# esp-tom.net
KiCad netlist of a schematic drawn in EAGLE
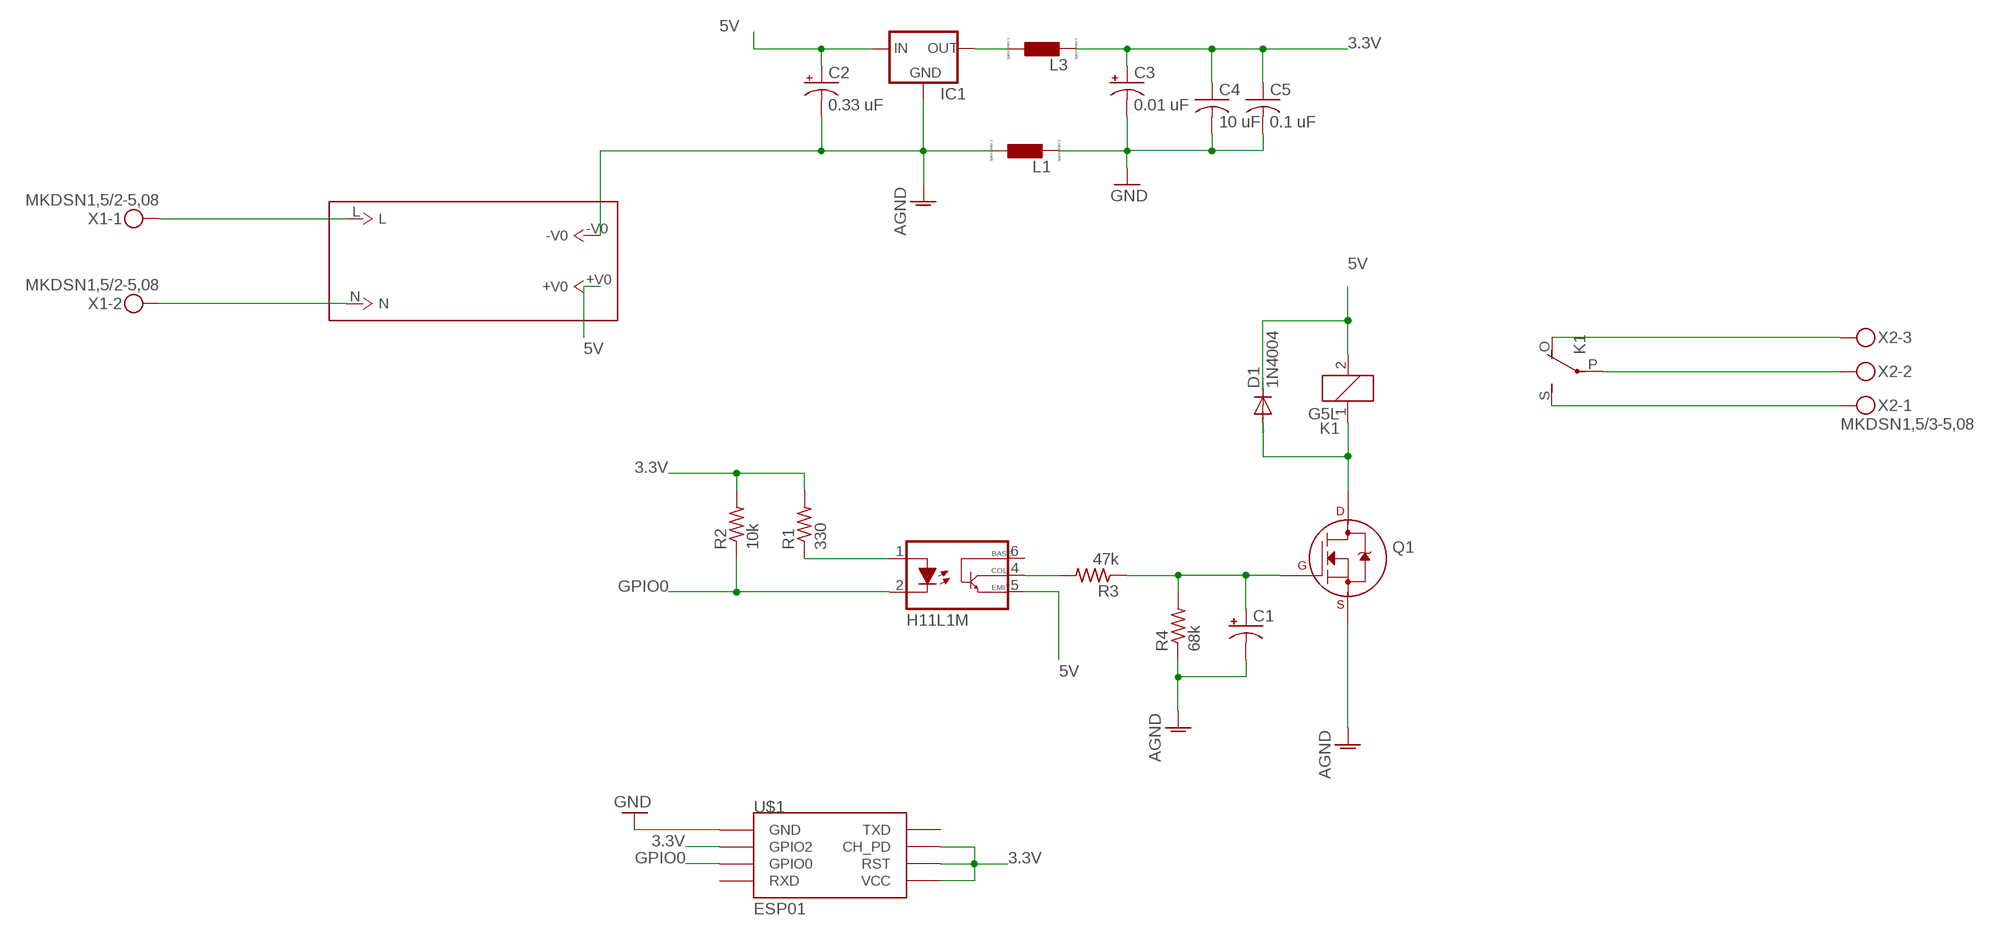
[diagram p0: schematic, sheet 1]

(export (version "E")
  (design (tool "Eeschema 10.0.6"))
  (components
    (comp (ref "C1")
      (value "CPOL-USE2-5")
      (footprint "eagle-import:E2-5")
      (libsource (lib "eagle-import") (part "CPOL-USE2-5"))
    )
    (comp (ref "C2")
      (value "0.33 uF")
      (footprint "eagle-import:E2-5")
      (libsource (lib "eagle-import") (part "CPOL-USE2-5"))
    )
    (comp (ref "C3")
      (value "0.01 uF")
      (footprint "eagle-import:E2-5")
      (libsource (lib "eagle-import") (part "CPOL-USE2-5"))
    )
    (comp (ref "C4")
      (value "10 uF")
      (footprint "eagle-import:C025-024X044")
      (libsource (lib "eagle-import") (part "C-US025-024X044"))
    )
    (comp (ref "C5")
      (value "0.1 uF")
      (footprint "eagle-import:C025-024X044")
      (libsource (lib "eagle-import") (part "C-US025-024X044"))
    )
    (comp (ref "D1")
      (value "1N4004")
      (footprint "eagle-import:DO41-10")
      (libsource (lib "eagle-import") (part "1N4004"))
    )
    (comp (ref "IC1")
      (value "78LXX")
      (footprint "eagle-import:78LXX")
      (libsource (lib "eagle-import") (part "78LXX"))
    )
    (comp (ref "K1")
      (value "G5L")
      (footprint "eagle-import:G5LE")
      (libsource (lib "eagle-import") (part "G5L"))
    )
    (comp (ref "L1")
      (value "L0207/10")
      (footprint "eagle-import:0207_10")
      (libsource (lib "eagle-import") (part "L0207/10"))
    )
    (comp (ref "L3")
      (value "L0207/10")
      (footprint "eagle-import:0207_10")
      (libsource (lib "eagle-import") (part "L0207/10"))
    )
    (comp (ref "OK1")
      (value "H11L1M")
      (footprint "eagle-import:DIL06")
      (fields (field (name "MF") "FAIRCHILD SEMICONDUCTOR") (field (name "MPN") "H11L1-M"))
      (libsource (lib "eagle-import") (part "H11LM1"))
    )
    (comp (ref "Q1")
      (value "2N7000_TO92")
      (footprint "eagle-import:TO-92")
      (libsource (lib "eagle-import") (part "2N700_TO920"))
    )
    (comp (ref "R1")
      (value "330")
      (footprint "eagle-import:0204_7")
      (libsource (lib "eagle-import") (part "R-US_0204/7"))
    )
    (comp (ref "R2")
      (value "10k")
      (footprint "eagle-import:0204_7")
      (libsource (lib "eagle-import") (part "R-US_0204/7"))
    )
    (comp (ref "R3")
      (value "47k")
      (footprint "eagle-import:0204_7")
      (libsource (lib "eagle-import") (part "R-US_0204/7"))
    )
    (comp (ref "R4")
      (value "68k")
      (footprint "eagle-import:0204_7")
      (libsource (lib "eagle-import") (part "R-US_0204/7"))
    )
    (comp (ref "U$1")
      (value "ESP01")
      (footprint "eagle-import:ESP01")
      (libsource (lib "eagle-import") (part "ESP01"))
    )
    (comp (ref "U$2")
      (value "NA03-T2S05")
      (footprint "eagle-import:NA03-T2S05")
      (libsource (lib "eagle-import") (part "NA03-T2S05"))
    )
    (comp (ref "X1")
      (value "MKDSN1,5/2-5,08")
      (footprint "eagle-import:MKDSN1,5_2-5,08")
      (libsource (lib "eagle-import") (part "MKDSN1,5/2-5,08"))
    )
    (comp (ref "X2")
      (value "MKDSN1,5/3-5,08")
      (footprint "eagle-import:MKDSN1,5_3-5,08")
      (libsource (lib "eagle-import") (part "MKDSN1,5/3-5,08"))
    )
  )
  (nets
    (net (code "1") (name "/3.3V") (class "Default")
      (node (ref "C3") (pin "+") (pinfunction "+_+") (pintype "passive"))
      (node (ref "C4") (pin "1") (pinfunction "1_1") (pintype "passive"))
      (node (ref "C5") (pin "1") (pinfunction "1_1") (pintype "passive"))
      (node (ref "L3") (pin "2") (pinfunction "2_2") (pintype "passive"))
      (node (ref "R1") (pin "2") (pinfunction "2_2") (pintype "passive"))
      (node (ref "R2") (pin "2") (pinfunction "2_2") (pintype "passive"))
      (node (ref "U$1") (pin "CH_PD") (pinfunction "CH_PD_CH_PD") (pintype "bidirectional"))
      (node (ref "U$1") (pin "GPIO2") (pinfunction "GPIO2_GPIO2") (pintype "bidirectional"))
      (node (ref "U$1") (pin "RST") (pinfunction "RST_RST") (pintype "bidirectional"))
      (node (ref "U$1") (pin "VCC") (pinfunction "VCC_VCC") (pintype "bidirectional"))
    )
    (net (code "2") (name "/5V") (class "Default")
      (node (ref "C2") (pin "+") (pinfunction "+_+") (pintype "passive"))
      (node (ref "D1") (pin "C") (pinfunction "C_C") (pintype "passive"))
      (node (ref "IC1") (pin "IN") (pinfunction "IN_IN") (pintype "input"))
      (node (ref "K1") (pin "2") (pinfunction "2_2") (pintype "passive"))
      (node (ref "OK1") (pin "5") (pinfunction "GND_5") (pintype "power_in"))
      (node (ref "U$2") (pin "+V0") (pinfunction "+V0_+V0") (pintype "bidirectional"))
    )
    (net (code "3") (name "/GPIO0") (class "Default")
      (node (ref "OK1") (pin "2") (pinfunction "C_2") (pintype "passive"))
      (node (ref "R2") (pin "1") (pinfunction "1_1") (pintype "passive"))
      (node (ref "U$1") (pin "GPIO0") (pinfunction "GPIO0_GPIO0") (pintype "bidirectional"))
    )
    (net (code "4") (name "/VCC") (class "Default")
      (node (ref "OK1") (pin "6") (pinfunction "VCC_6") (pintype "power_in"))
    )
    (net (code "5") (name "AGND") (class "Default")
      (node (ref "C1") (pin "-") (pinfunction "-_-") (pintype "passive"))
      (node (ref "C2") (pin "-") (pinfunction "-_-") (pintype "passive"))
      (node (ref "IC1") (pin "GND") (pinfunction "GND_GND") (pintype "input"))
      (node (ref "L1") (pin "1") (pinfunction "1_1") (pintype "passive"))
      (node (ref "Q1") (pin "1") (pinfunction "S_1") (pintype "bidirectional"))
      (node (ref "R4") (pin "1") (pinfunction "1_1") (pintype "passive"))
      (node (ref "U$2") (pin "-V0") (pinfunction "-V0_-V0") (pintype "bidirectional"))
    )
    (net (code "6") (name "GND") (class "Default")
      (node (ref "C3") (pin "-") (pinfunction "-_-") (pintype "passive"))
      (node (ref "C4") (pin "2") (pinfunction "2_2") (pintype "passive"))
      (node (ref "C5") (pin "2") (pinfunction "2_2") (pintype "passive"))
      (node (ref "L1") (pin "2") (pinfunction "2_2") (pintype "passive"))
      (node (ref "U$1") (pin "GND") (pinfunction "GND_GND") (pintype "bidirectional"))
    )
    (net (code "7") (name "Net-(IC1-PadOUT)") (class "Default")
      (node (ref "IC1") (pin "OUT") (pinfunction "OUT_OUT") (pintype "passive"))
      (node (ref "L3") (pin "1") (pinfunction "1_1") (pintype "passive"))
    )
    (net (code "8") (name "Net-(OK1-A)") (class "Default")
      (node (ref "OK1") (pin "1") (pinfunction "A_1") (pintype "passive"))
      (node (ref "R1") (pin "1") (pinfunction "1_1") (pintype "passive"))
    )
    (net (code "9") (name "Net-(OK1-OUT)") (class "Default")
      (node (ref "OK1") (pin "4") (pinfunction "OUT_4") (pintype "output"))
      (node (ref "R3") (pin "2") (pinfunction "2_2") (pintype "passive"))
    )
    (net (code "10") (name "Net-(Q1-D)") (class "Default")
      (node (ref "D1") (pin "A") (pinfunction "A_A") (pintype "passive"))
      (node (ref "K1") (pin "1") (pinfunction "1_1") (pintype "passive"))
      (node (ref "Q1") (pin "3") (pinfunction "D_3") (pintype "bidirectional"))
    )
    (net (code "11") (name "Net-(Q1-G)") (class "Default")
      (node (ref "C1") (pin "+") (pinfunction "+_+") (pintype "passive"))
      (node (ref "Q1") (pin "2") (pinfunction "G_2") (pintype "tri_state"))
      (node (ref "R3") (pin "1") (pinfunction "1_1") (pintype "passive"))
      (node (ref "R4") (pin "2") (pinfunction "2_2") (pintype "passive"))
    )
    (net (code "12") (name "Net-(X1A-KL)") (class "Default")
      (node (ref "U$2") (pin "L") (pinfunction "L_L") (pintype "bidirectional"))
      (node (ref "X1") (pin "1") (pinfunction "KL_1") (pintype "passive"))
    )
    (net (code "13") (name "Net-(X1B-KL)") (class "Default")
      (node (ref "U$2") (pin "N") (pinfunction "N_N") (pintype "bidirectional"))
      (node (ref "X1") (pin "2") (pinfunction "KL_2") (pintype "passive"))
    )
    (net (code "14") (name "Net-(X2A-KL)") (class "Default")
      (node (ref "K1") (pin "S") (pinfunction "S_S") (pintype "passive"))
      (node (ref "X2") (pin "1") (pinfunction "KL_1") (pintype "passive"))
    )
    (net (code "15") (name "Net-(X2B-KL)") (class "Default")
      (node (ref "K1") (pin "P") (pinfunction "P_P") (pintype "passive"))
      (node (ref "X2") (pin "2") (pinfunction "KL_2") (pintype "passive"))
    )
    (net (code "16") (name "Net-(X2C-KL)") (class "Default")
      (node (ref "K1") (pin "O") (pinfunction "O_O") (pintype "passive"))
      (node (ref "X2") (pin "3") (pinfunction "KL_3") (pintype "passive"))
    )
    (net (code "17") (name "unconnected-(U$1-RXD-PadRX)") (class "Default")
      (node (ref "U$1") (pin "RX") (pinfunction "RXD_RX") (pintype "bidirectional"))
    )
    (net (code "18") (name "unconnected-(U$1-TXD-PadTX)") (class "Default")
      (node (ref "U$1") (pin "TX") (pinfunction "TXD_TX") (pintype "bidirectional"))
    )
  )
)
